# Hall_Effect_Sensors_Panel.net
KiCad netlist of a schematic drawn in Altium Designer
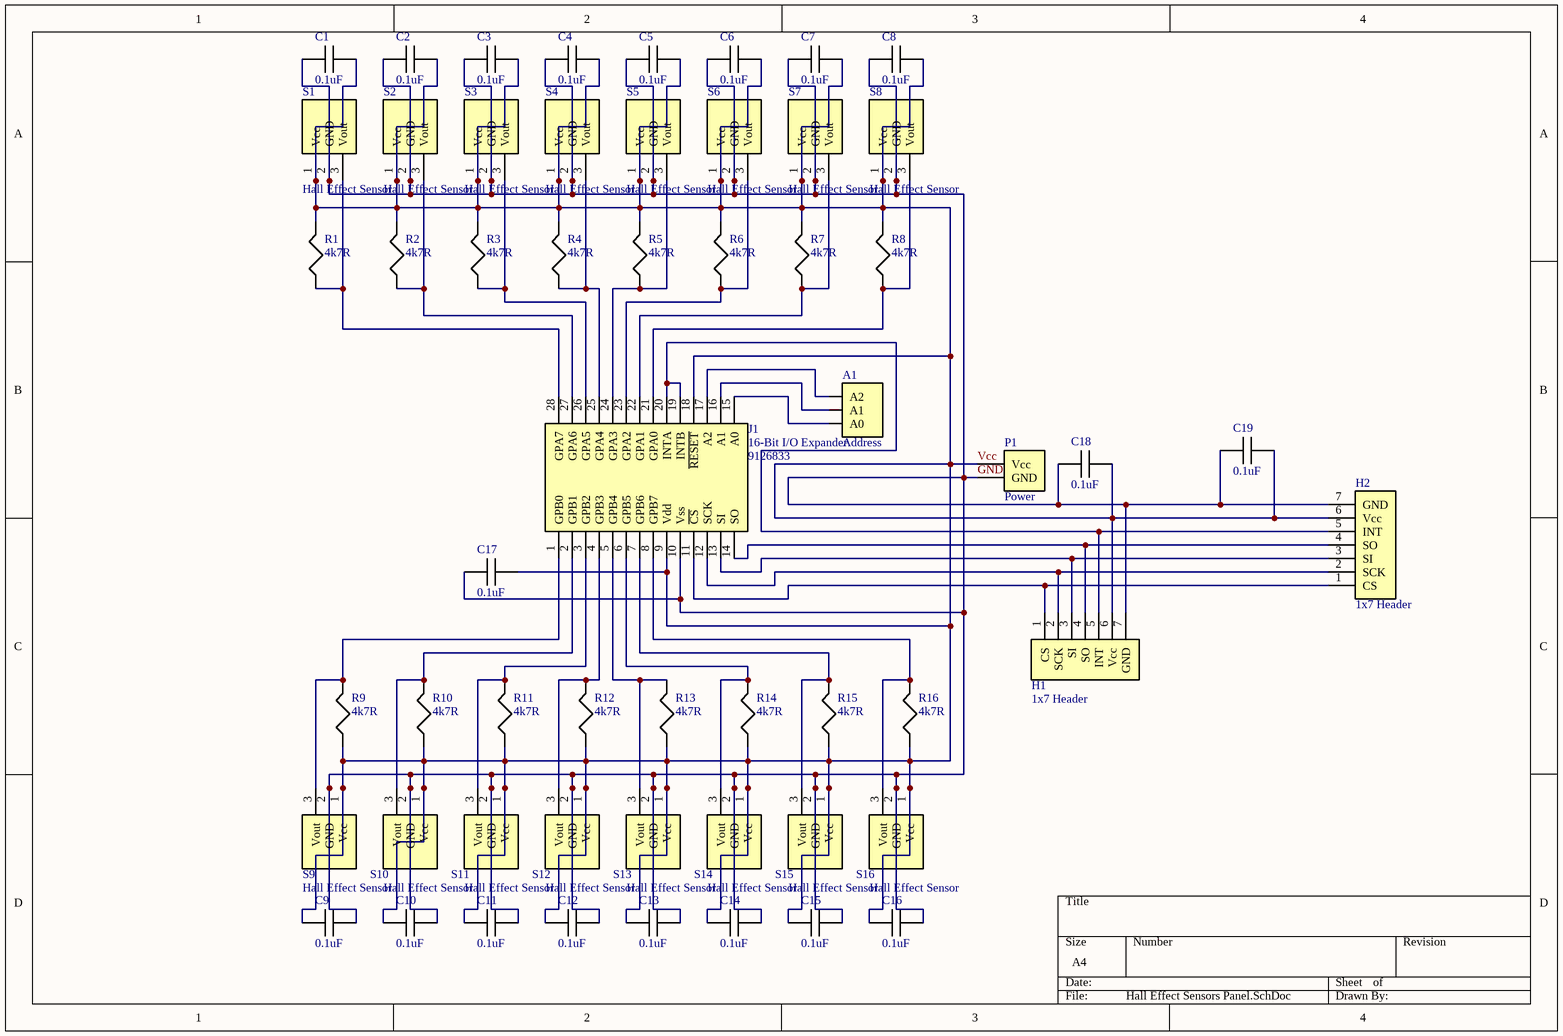
[diagram p0: Hall Effect Sensors Panel.SchDoc]

(export (version "E")
  (design (tool "Eeschema 10.0.6"))
  (components
    (comp (ref "A1")
      (value "Address")
      (footprint "Address")
      (libsource (lib "Hall Effect Sensor Panel Lib") (part "Address"))
    )
    (comp (ref "C1")
      (value "0.1uF")
      (footprint "C320C104K5R5TA")
      (fields
        (field (name "MANUFACTURER") "KEMET")
        (field (name "MANUFACTURER PART NUMBER") "C320C104K5R5TA")
        (field (name "TOLERANCE") "10%")
      )
      (libsource (lib "Hall Effect Sensor Panel Lib") (part "C320C104K5R5TA"))
    )
    (comp (ref "C2")
      (value "0.1uF")
      (footprint "C320C104K5R5TA")
      (fields
        (field (name "MANUFACTURER") "KEMET")
        (field (name "MANUFACTURER PART NUMBER") "C320C104K5R5TA")
        (field (name "TOLERANCE") "10%")
      )
      (libsource (lib "Hall Effect Sensor Panel Lib") (part "C320C104K5R5TA"))
    )
    (comp (ref "C3")
      (value "0.1uF")
      (footprint "C320C104K5R5TA")
      (fields
        (field (name "MANUFACTURER") "KEMET")
        (field (name "MANUFACTURER PART NUMBER") "C320C104K5R5TA")
        (field (name "TOLERANCE") "10%")
      )
      (libsource (lib "Hall Effect Sensor Panel Lib") (part "C320C104K5R5TA"))
    )
    (comp (ref "C4")
      (value "0.1uF")
      (footprint "C320C104K5R5TA")
      (fields
        (field (name "MANUFACTURER") "KEMET")
        (field (name "MANUFACTURER PART NUMBER") "C320C104K5R5TA")
        (field (name "TOLERANCE") "10%")
      )
      (libsource (lib "Hall Effect Sensor Panel Lib") (part "C320C104K5R5TA"))
    )
    (comp (ref "C5")
      (value "0.1uF")
      (footprint "C320C104K5R5TA")
      (fields
        (field (name "MANUFACTURER") "KEMET")
        (field (name "MANUFACTURER PART NUMBER") "C320C104K5R5TA")
        (field (name "TOLERANCE") "10%")
      )
      (libsource (lib "Hall Effect Sensor Panel Lib") (part "C320C104K5R5TA"))
    )
    (comp (ref "C6")
      (value "0.1uF")
      (footprint "C320C104K5R5TA")
      (fields
        (field (name "MANUFACTURER") "KEMET")
        (field (name "MANUFACTURER PART NUMBER") "C320C104K5R5TA")
        (field (name "TOLERANCE") "10%")
      )
      (libsource (lib "Hall Effect Sensor Panel Lib") (part "C320C104K5R5TA"))
    )
    (comp (ref "C7")
      (value "0.1uF")
      (footprint "C320C104K5R5TA")
      (fields
        (field (name "MANUFACTURER") "KEMET")
        (field (name "MANUFACTURER PART NUMBER") "C320C104K5R5TA")
        (field (name "TOLERANCE") "10%")
      )
      (libsource (lib "Hall Effect Sensor Panel Lib") (part "C320C104K5R5TA"))
    )
    (comp (ref "C8")
      (value "0.1uF")
      (footprint "C320C104K5R5TA")
      (fields
        (field (name "MANUFACTURER") "KEMET")
        (field (name "MANUFACTURER PART NUMBER") "C320C104K5R5TA")
        (field (name "TOLERANCE") "10%")
      )
      (libsource (lib "Hall Effect Sensor Panel Lib") (part "C320C104K5R5TA"))
    )
    (comp (ref "C9")
      (value "0.1uF")
      (footprint "C320C104K5R5TA")
      (fields
        (field (name "MANUFACTURER") "KEMET")
        (field (name "MANUFACTURER PART NUMBER") "C320C104K5R5TA")
        (field (name "TOLERANCE") "10%")
      )
      (libsource (lib "Hall Effect Sensor Panel Lib") (part "C320C104K5R5TA"))
    )
    (comp (ref "C10")
      (value "0.1uF")
      (footprint "C320C104K5R5TA")
      (fields
        (field (name "MANUFACTURER") "KEMET")
        (field (name "MANUFACTURER PART NUMBER") "C320C104K5R5TA")
        (field (name "TOLERANCE") "10%")
      )
      (libsource (lib "Hall Effect Sensor Panel Lib") (part "C320C104K5R5TA"))
    )
    (comp (ref "C11")
      (value "0.1uF")
      (footprint "C320C104K5R5TA")
      (fields
        (field (name "MANUFACTURER") "KEMET")
        (field (name "MANUFACTURER PART NUMBER") "C320C104K5R5TA")
        (field (name "TOLERANCE") "10%")
      )
      (libsource (lib "Hall Effect Sensor Panel Lib") (part "C320C104K5R5TA"))
    )
    (comp (ref "C12")
      (value "0.1uF")
      (footprint "C320C104K5R5TA")
      (fields
        (field (name "MANUFACTURER") "KEMET")
        (field (name "MANUFACTURER PART NUMBER") "C320C104K5R5TA")
        (field (name "TOLERANCE") "10%")
      )
      (libsource (lib "Hall Effect Sensor Panel Lib") (part "C320C104K5R5TA"))
    )
    (comp (ref "C13")
      (value "0.1uF")
      (footprint "C320C104K5R5TA")
      (fields
        (field (name "MANUFACTURER") "KEMET")
        (field (name "MANUFACTURER PART NUMBER") "C320C104K5R5TA")
        (field (name "TOLERANCE") "10%")
      )
      (libsource (lib "Hall Effect Sensor Panel Lib") (part "C320C104K5R5TA"))
    )
    (comp (ref "C14")
      (value "0.1uF")
      (footprint "C320C104K5R5TA")
      (fields
        (field (name "MANUFACTURER") "KEMET")
        (field (name "MANUFACTURER PART NUMBER") "C320C104K5R5TA")
        (field (name "TOLERANCE") "10%")
      )
      (libsource (lib "Hall Effect Sensor Panel Lib") (part "C320C104K5R5TA"))
    )
    (comp (ref "C15")
      (value "0.1uF")
      (footprint "C320C104K5R5TA")
      (fields
        (field (name "MANUFACTURER") "KEMET")
        (field (name "MANUFACTURER PART NUMBER") "C320C104K5R5TA")
        (field (name "TOLERANCE") "10%")
      )
      (libsource (lib "Hall Effect Sensor Panel Lib") (part "C320C104K5R5TA"))
    )
    (comp (ref "C16")
      (value "0.1uF")
      (footprint "C320C104K5R5TA")
      (fields
        (field (name "MANUFACTURER") "KEMET")
        (field (name "MANUFACTURER PART NUMBER") "C320C104K5R5TA")
        (field (name "TOLERANCE") "10%")
      )
      (libsource (lib "Hall Effect Sensor Panel Lib") (part "C320C104K5R5TA"))
    )
    (comp (ref "C17")
      (value "0.1uF")
      (footprint "C320C104K5R5TA")
      (fields
        (field (name "MANUFACTURER") "KEMET")
        (field (name "MANUFACTURER PART NUMBER") "C320C104K5R5TA")
        (field (name "TOLERANCE") "10%")
      )
      (libsource (lib "Hall Effect Sensor Panel Lib") (part "C320C104K5R5TA"))
    )
    (comp (ref "C18")
      (value "0.1uF")
      (footprint "C320C104K5R5TA")
      (fields
        (field (name "MANUFACTURER") "KEMET")
        (field (name "MANUFACTURER PART NUMBER") "C320C104K5R5TA")
        (field (name "TOLERANCE") "10%")
      )
      (libsource (lib "Hall Effect Sensor Panel Lib") (part "C320C104K5R5TA"))
    )
    (comp (ref "C19")
      (value "0.1uF")
      (footprint "C320C104K5R5TA")
      (fields
        (field (name "MANUFACTURER") "KEMET")
        (field (name "MANUFACTURER PART NUMBER") "C320C104K5R5TA")
        (field (name "TOLERANCE") "10%")
      )
      (libsource (lib "Hall Effect Sensor Panel Lib") (part "C320C104K5R5TA"))
    )
    (comp (ref "H1")
      (value "1x7 Header")
      (footprint "Molex")
      (description "CONN HEADER VERT 7POS 2.54MM")
      (fields (field (name "MANUFACTURER") "Molex") (field (name "MANUFACTURER PART NUMBER") "22-23-2071"))
      (libsource (lib "") (part "22-23-2071_1"))
    )
    (comp (ref "H2")
      (value "1x7 Header")
      (footprint "Molex")
      (description "CONN HEADER VERT 7POS 2.54MM")
      (fields (field (name "MANUFACTURER") "Molex") (field (name "MANUFACTURER PART NUMBER") "22-23-2071"))
      (libsource (lib "Hall Effect Sensor Panel Lib") (part "22-23-2071"))
    )
    (comp (ref "J1")
      (value "16-Bit I/O Expander")
      (footprint "MCP23S17-E/SP")
      (fields
        (field (name "MANUFACTURER") "Microchip")
        (field (name "MANUFACTURER PART NUMBER") "MCP23S17-E/SP")
        (field (name "SUPPLIER PART NUMBER 1") "9126833")
        (field (name "TOLERANCE") "5%")
      )
      (libsource (lib "Hall Effect Sensor Panel Lib") (part "MCP23S17-E/SP"))
    )
    (comp (ref "P1")
      (value "Power")
      (footprint "Power")
      (libsource (lib "Hall Effect Sensor Panel Lib") (part "Power"))
    )
    (comp (ref "R1")
      (value "4k7R")
      (footprint "CFR100J4K7")
      (fields
        (field (name "MANUFACTURER") "TE Connectivity")
        (field (name "MANUFACTURER PART NUMBER") "CFR100J4K7")
        (field (name "TOLERANCE") "5%")
      )
      (libsource (lib "Hall Effect Sensor Panel Lib") (part "CFR100J4K7"))
    )
    (comp (ref "R2")
      (value "4k7R")
      (footprint "CFR100J4K7")
      (fields
        (field (name "MANUFACTURER") "TE Connectivity")
        (field (name "MANUFACTURER PART NUMBER") "CFR100J4K7")
        (field (name "TOLERANCE") "5%")
      )
      (libsource (lib "Hall Effect Sensor Panel Lib") (part "CFR100J4K7"))
    )
    (comp (ref "R3")
      (value "4k7R")
      (footprint "CFR100J4K7")
      (fields
        (field (name "MANUFACTURER") "TE Connectivity")
        (field (name "MANUFACTURER PART NUMBER") "CFR100J4K7")
        (field (name "TOLERANCE") "5%")
      )
      (libsource (lib "Hall Effect Sensor Panel Lib") (part "CFR100J4K7"))
    )
    (comp (ref "R4")
      (value "4k7R")
      (footprint "CFR100J4K7")
      (fields
        (field (name "MANUFACTURER") "TE Connectivity")
        (field (name "MANUFACTURER PART NUMBER") "CFR100J4K7")
        (field (name "TOLERANCE") "5%")
      )
      (libsource (lib "Hall Effect Sensor Panel Lib") (part "CFR100J4K7"))
    )
    (comp (ref "R5")
      (value "4k7R")
      (footprint "CFR100J4K7")
      (fields
        (field (name "MANUFACTURER") "TE Connectivity")
        (field (name "MANUFACTURER PART NUMBER") "CFR100J4K7")
        (field (name "TOLERANCE") "5%")
      )
      (libsource (lib "Hall Effect Sensor Panel Lib") (part "CFR100J4K7"))
    )
    (comp (ref "R6")
      (value "4k7R")
      (footprint "CFR100J4K7")
      (fields
        (field (name "MANUFACTURER") "TE Connectivity")
        (field (name "MANUFACTURER PART NUMBER") "CFR100J4K7")
        (field (name "TOLERANCE") "5%")
      )
      (libsource (lib "Hall Effect Sensor Panel Lib") (part "CFR100J4K7"))
    )
    (comp (ref "R7")
      (value "4k7R")
      (footprint "CFR100J4K7")
      (fields
        (field (name "MANUFACTURER") "TE Connectivity")
        (field (name "MANUFACTURER PART NUMBER") "CFR100J4K7")
        (field (name "TOLERANCE") "5%")
      )
      (libsource (lib "Hall Effect Sensor Panel Lib") (part "CFR100J4K7"))
    )
    (comp (ref "R8")
      (value "4k7R")
      (footprint "CFR100J4K7")
      (fields
        (field (name "MANUFACTURER") "TE Connectivity")
        (field (name "MANUFACTURER PART NUMBER") "CFR100J4K7")
        (field (name "TOLERANCE") "5%")
      )
      (libsource (lib "Hall Effect Sensor Panel Lib") (part "CFR100J4K7"))
    )
    (comp (ref "R9")
      (value "4k7R")
      (footprint "CFR100J4K7")
      (fields
        (field (name "MANUFACTURER") "TE Connectivity")
        (field (name "MANUFACTURER PART NUMBER") "CFR100J4K7")
        (field (name "TOLERANCE") "5%")
      )
      (libsource (lib "Hall Effect Sensor Panel Lib") (part "CFR100J4K7"))
    )
    (comp (ref "R10")
      (value "4k7R")
      (footprint "CFR100J4K7")
      (fields
        (field (name "MANUFACTURER") "TE Connectivity")
        (field (name "MANUFACTURER PART NUMBER") "CFR100J4K7")
        (field (name "TOLERANCE") "5%")
      )
      (libsource (lib "Hall Effect Sensor Panel Lib") (part "CFR100J4K7"))
    )
    (comp (ref "R11")
      (value "4k7R")
      (footprint "CFR100J4K7")
      (fields
        (field (name "MANUFACTURER") "TE Connectivity")
        (field (name "MANUFACTURER PART NUMBER") "CFR100J4K7")
        (field (name "TOLERANCE") "5%")
      )
      (libsource (lib "Hall Effect Sensor Panel Lib") (part "CFR100J4K7"))
    )
    (comp (ref "R12")
      (value "4k7R")
      (footprint "CFR100J4K7")
      (fields
        (field (name "MANUFACTURER") "TE Connectivity")
        (field (name "MANUFACTURER PART NUMBER") "CFR100J4K7")
        (field (name "TOLERANCE") "5%")
      )
      (libsource (lib "Hall Effect Sensor Panel Lib") (part "CFR100J4K7"))
    )
    (comp (ref "R13")
      (value "4k7R")
      (footprint "CFR100J4K7")
      (fields
        (field (name "MANUFACTURER") "TE Connectivity")
        (field (name "MANUFACTURER PART NUMBER") "CFR100J4K7")
        (field (name "TOLERANCE") "5%")
      )
      (libsource (lib "Hall Effect Sensor Panel Lib") (part "CFR100J4K7"))
    )
    (comp (ref "R14")
      (value "4k7R")
      (footprint "CFR100J4K7")
      (fields
        (field (name "MANUFACTURER") "TE Connectivity")
        (field (name "MANUFACTURER PART NUMBER") "CFR100J4K7")
        (field (name "TOLERANCE") "5%")
      )
      (libsource (lib "Hall Effect Sensor Panel Lib") (part "CFR100J4K7"))
    )
    (comp (ref "R15")
      (value "4k7R")
      (footprint "CFR100J4K7")
      (fields
        (field (name "MANUFACTURER") "TE Connectivity")
        (field (name "MANUFACTURER PART NUMBER") "CFR100J4K7")
        (field (name "TOLERANCE") "5%")
      )
      (libsource (lib "Hall Effect Sensor Panel Lib") (part "CFR100J4K7"))
    )
    (comp (ref "R16")
      (value "4k7R")
      (footprint "CFR100J4K7")
      (fields
        (field (name "MANUFACTURER") "TE Connectivity")
        (field (name "MANUFACTURER PART NUMBER") "CFR100J4K7")
        (field (name "TOLERANCE") "5%")
      )
      (libsource (lib "Hall Effect Sensor Panel Lib") (part "CFR100J4K7"))
    )
    (comp (ref "S1")
      (value "Hall Effect Sensor")
      (footprint "A1104EUA-T")
      (description "ALLEGRO MICROSYSTEMS - A1104EUA-T - IC, HALL-EFFECT SWITCH SIP-3")
      (fields
        (field (name "MANUFACTURER") "Allegro MicroSystems")
        (field (name "MANUFACTURER PART NUMBER") "A1104EUA-T")
      )
      (libsource (lib "Hall Effect Sensor Panel Lib") (part "A1104EUA-T"))
    )
    (comp (ref "S2")
      (value "Hall Effect Sensor")
      (footprint "A1104EUA-T")
      (description "ALLEGRO MICROSYSTEMS - A1104EUA-T - IC, HALL-EFFECT SWITCH SIP-3")
      (fields
        (field (name "MANUFACTURER") "Allegro MicroSystems")
        (field (name "MANUFACTURER PART NUMBER") "A1104EUA-T")
      )
      (libsource (lib "Hall Effect Sensor Panel Lib") (part "A1104EUA-T"))
    )
    (comp (ref "S3")
      (value "Hall Effect Sensor")
      (footprint "A1104EUA-T")
      (description "ALLEGRO MICROSYSTEMS - A1104EUA-T - IC, HALL-EFFECT SWITCH SIP-3")
      (fields
        (field (name "MANUFACTURER") "Allegro MicroSystems")
        (field (name "MANUFACTURER PART NUMBER") "A1104EUA-T")
      )
      (libsource (lib "Hall Effect Sensor Panel Lib") (part "A1104EUA-T"))
    )
    (comp (ref "S4")
      (value "Hall Effect Sensor")
      (footprint "A1104EUA-T")
      (description "ALLEGRO MICROSYSTEMS - A1104EUA-T - IC, HALL-EFFECT SWITCH SIP-3")
      (fields
        (field (name "MANUFACTURER") "Allegro MicroSystems")
        (field (name "MANUFACTURER PART NUMBER") "A1104EUA-T")
      )
      (libsource (lib "Hall Effect Sensor Panel Lib") (part "A1104EUA-T"))
    )
    (comp (ref "S5")
      (value "Hall Effect Sensor")
      (footprint "A1104EUA-T")
      (description "ALLEGRO MICROSYSTEMS - A1104EUA-T - IC, HALL-EFFECT SWITCH SIP-3")
      (fields
        (field (name "MANUFACTURER") "Allegro MicroSystems")
        (field (name "MANUFACTURER PART NUMBER") "A1104EUA-T")
      )
      (libsource (lib "Hall Effect Sensor Panel Lib") (part "A1104EUA-T"))
    )
    (comp (ref "S6")
      (value "Hall Effect Sensor")
      (footprint "A1104EUA-T")
      (description "ALLEGRO MICROSYSTEMS - A1104EUA-T - IC, HALL-EFFECT SWITCH SIP-3")
      (fields
        (field (name "MANUFACTURER") "Allegro MicroSystems")
        (field (name "MANUFACTURER PART NUMBER") "A1104EUA-T")
      )
      (libsource (lib "Hall Effect Sensor Panel Lib") (part "A1104EUA-T"))
    )
    (comp (ref "S7")
      (value "Hall Effect Sensor")
      (footprint "A1104EUA-T")
      (description "ALLEGRO MICROSYSTEMS - A1104EUA-T - IC, HALL-EFFECT SWITCH SIP-3")
      (fields
        (field (name "MANUFACTURER") "Allegro MicroSystems")
        (field (name "MANUFACTURER PART NUMBER") "A1104EUA-T")
      )
      (libsource (lib "Hall Effect Sensor Panel Lib") (part "A1104EUA-T"))
    )
    (comp (ref "S8")
      (value "Hall Effect Sensor")
      (footprint "A1104EUA-T")
      (description "ALLEGRO MICROSYSTEMS - A1104EUA-T - IC, HALL-EFFECT SWITCH SIP-3")
      (fields
        (field (name "MANUFACTURER") "Allegro MicroSystems")
        (field (name "MANUFACTURER PART NUMBER") "A1104EUA-T")
      )
      (libsource (lib "Hall Effect Sensor Panel Lib") (part "A1104EUA-T"))
    )
    (comp (ref "S9")
      (value "Hall Effect Sensor")
      (footprint "A1104EUA-T")
      (description "ALLEGRO MICROSYSTEMS - A1104EUA-T - IC, HALL-EFFECT SWITCH SIP-3")
      (fields
        (field (name "MANUFACTURER") "Allegro MicroSystems")
        (field (name "MANUFACTURER PART NUMBER") "A1104EUA-T")
      )
      (libsource (lib "") (part "A1104EUA-T_1"))
    )
    (comp (ref "S10")
      (value "Hall Effect Sensor")
      (footprint "A1104EUA-T")
      (description "ALLEGRO MICROSYSTEMS - A1104EUA-T - IC, HALL-EFFECT SWITCH SIP-3")
      (fields
        (field (name "MANUFACTURER") "Allegro MicroSystems")
        (field (name "MANUFACTURER PART NUMBER") "A1104EUA-T")
      )
      (libsource (lib "") (part "A1104EUA-T_1"))
    )
    (comp (ref "S11")
      (value "Hall Effect Sensor")
      (footprint "A1104EUA-T")
      (description "ALLEGRO MICROSYSTEMS - A1104EUA-T - IC, HALL-EFFECT SWITCH SIP-3")
      (fields
        (field (name "MANUFACTURER") "Allegro MicroSystems")
        (field (name "MANUFACTURER PART NUMBER") "A1104EUA-T")
      )
      (libsource (lib "") (part "A1104EUA-T_1"))
    )
    (comp (ref "S12")
      (value "Hall Effect Sensor")
      (footprint "A1104EUA-T")
      (description "ALLEGRO MICROSYSTEMS - A1104EUA-T - IC, HALL-EFFECT SWITCH SIP-3")
      (fields
        (field (name "MANUFACTURER") "Allegro MicroSystems")
        (field (name "MANUFACTURER PART NUMBER") "A1104EUA-T")
      )
      (libsource (lib "") (part "A1104EUA-T_1"))
    )
    (comp (ref "S13")
      (value "Hall Effect Sensor")
      (footprint "A1104EUA-T")
      (description "ALLEGRO MICROSYSTEMS - A1104EUA-T - IC, HALL-EFFECT SWITCH SIP-3")
      (fields
        (field (name "MANUFACTURER") "Allegro MicroSystems")
        (field (name "MANUFACTURER PART NUMBER") "A1104EUA-T")
      )
      (libsource (lib "") (part "A1104EUA-T_1"))
    )
    (comp (ref "S14")
      (value "Hall Effect Sensor")
      (footprint "A1104EUA-T")
      (description "ALLEGRO MICROSYSTEMS - A1104EUA-T - IC, HALL-EFFECT SWITCH SIP-3")
      (fields
        (field (name "MANUFACTURER") "Allegro MicroSystems")
        (field (name "MANUFACTURER PART NUMBER") "A1104EUA-T")
      )
      (libsource (lib "") (part "A1104EUA-T_1"))
    )
    (comp (ref "S15")
      (value "Hall Effect Sensor")
      (footprint "A1104EUA-T")
      (description "ALLEGRO MICROSYSTEMS - A1104EUA-T - IC, HALL-EFFECT SWITCH SIP-3")
      (fields
        (field (name "MANUFACTURER") "Allegro MicroSystems")
        (field (name "MANUFACTURER PART NUMBER") "A1104EUA-T")
      )
      (libsource (lib "") (part "A1104EUA-T_1"))
    )
    (comp (ref "S16")
      (value "Hall Effect Sensor")
      (footprint "A1104EUA-T")
      (description "ALLEGRO MICROSYSTEMS - A1104EUA-T - IC, HALL-EFFECT SWITCH SIP-3")
      (fields
        (field (name "MANUFACTURER") "Allegro MicroSystems")
        (field (name "MANUFACTURER PART NUMBER") "A1104EUA-T")
      )
      (libsource (lib "") (part "A1104EUA-T_1"))
    )
  )
  (nets
    (net (code "1") (name "/GND") (class "Default")
      (node (ref "C1") (pin "1") (pinfunction "48_1") (pintype "passive"))
      (node (ref "C10") (pin "2") (pinfunction "2_2") (pintype "passive"))
      (node (ref "C11") (pin "2") (pinfunction "2_2") (pintype "passive"))
      (node (ref "C12") (pin "2") (pinfunction "2_2") (pintype "passive"))
      (node (ref "C13") (pin "2") (pinfunction "2_2") (pintype "passive"))
      (node (ref "C14") (pin "2") (pinfunction "2_2") (pintype "passive"))
      (node (ref "C15") (pin "2") (pinfunction "2_2") (pintype "passive"))
      (node (ref "C16") (pin "2") (pinfunction "2_2") (pintype "passive"))
      (node (ref "C17") (pin "1") (pinfunction "48_1") (pintype "passive"))
      (node (ref "C18") (pin "1") (pinfunction "48_1") (pintype "passive"))
      (node (ref "C19") (pin "1") (pinfunction "48_1") (pintype "passive"))
      (node (ref "C2") (pin "1") (pinfunction "48_1") (pintype "passive"))
      (node (ref "C3") (pin "1") (pinfunction "48_1") (pintype "passive"))
      (node (ref "C4") (pin "1") (pinfunction "48_1") (pintype "passive"))
      (node (ref "C5") (pin "1") (pinfunction "48_1") (pintype "passive"))
      (node (ref "C6") (pin "1") (pinfunction "48_1") (pintype "passive"))
      (node (ref "C7") (pin "1") (pinfunction "48_1") (pintype "passive"))
      (node (ref "C8") (pin "1") (pinfunction "48_1") (pintype "passive"))
      (node (ref "C9") (pin "2") (pinfunction "2_2") (pintype "passive"))
      (node (ref "H1") (pin "7") (pinfunction "GND_7") (pintype "passive"))
      (node (ref "H2") (pin "7") (pinfunction "GND_7") (pintype "passive"))
      (node (ref "J1") (pin "10") (pinfunction "Vss_10") (pintype "passive"))
      (node (ref "P1") (pin "2") (pinfunction "GND_2") (pintype "passive"))
      (node (ref "S1") (pin "2") (pinfunction "GND_2") (pintype "passive"))
      (node (ref "S10") (pin "2") (pinfunction "GND_2") (pintype "passive"))
      (node (ref "S11") (pin "2") (pinfunction "GND_2") (pintype "passive"))
      (node (ref "S12") (pin "2") (pinfunction "GND_2") (pintype "passive"))
      (node (ref "S13") (pin "2") (pinfunction "GND_2") (pintype "passive"))
      (node (ref "S14") (pin "2") (pinfunction "GND_2") (pintype "passive"))
      (node (ref "S15") (pin "2") (pinfunction "GND_2") (pintype "passive"))
      (node (ref "S16") (pin "2") (pinfunction "GND_2") (pintype "passive"))
      (node (ref "S2") (pin "2") (pinfunction "GND_2") (pintype "passive"))
      (node (ref "S3") (pin "2") (pinfunction "GND_2") (pintype "passive"))
      (node (ref "S4") (pin "2") (pinfunction "GND_2") (pintype "passive"))
      (node (ref "S5") (pin "2") (pinfunction "GND_2") (pintype "passive"))
      (node (ref "S6") (pin "2") (pinfunction "GND_2") (pintype "passive"))
      (node (ref "S7") (pin "2") (pinfunction "GND_2") (pintype "passive"))
      (node (ref "S8") (pin "2") (pinfunction "GND_2") (pintype "passive"))
      (node (ref "S9") (pin "2") (pinfunction "GND_2") (pintype "passive"))
    )
    (net (code "2") (name "/Vcc") (class "Default")
      (node (ref "C1") (pin "2") (pinfunction "2_2") (pintype "passive"))
      (node (ref "C10") (pin "1") (pinfunction "48_1") (pintype "passive"))
      (node (ref "C11") (pin "1") (pinfunction "48_1") (pintype "passive"))
      (node (ref "C12") (pin "1") (pinfunction "48_1") (pintype "passive"))
      (node (ref "C13") (pin "1") (pinfunction "48_1") (pintype "passive"))
      (node (ref "C14") (pin "1") (pinfunction "48_1") (pintype "passive"))
      (node (ref "C15") (pin "1") (pinfunction "48_1") (pintype "passive"))
      (node (ref "C16") (pin "1") (pinfunction "48_1") (pintype "passive"))
      (node (ref "C17") (pin "2") (pinfunction "2_2") (pintype "passive"))
      (node (ref "C18") (pin "2") (pinfunction "2_2") (pintype "passive"))
      (node (ref "C19") (pin "2") (pinfunction "2_2") (pintype "passive"))
      (node (ref "C2") (pin "2") (pinfunction "2_2") (pintype "passive"))
      (node (ref "C3") (pin "2") (pinfunction "2_2") (pintype "passive"))
      (node (ref "C4") (pin "2") (pinfunction "2_2") (pintype "passive"))
      (node (ref "C5") (pin "2") (pinfunction "2_2") (pintype "passive"))
      (node (ref "C6") (pin "2") (pinfunction "2_2") (pintype "passive"))
      (node (ref "C7") (pin "2") (pinfunction "2_2") (pintype "passive"))
      (node (ref "C8") (pin "2") (pinfunction "2_2") (pintype "passive"))
      (node (ref "C9") (pin "1") (pinfunction "48_1") (pintype "passive"))
      (node (ref "H1") (pin "6") (pinfunction "Vcc_6") (pintype "passive"))
      (node (ref "H2") (pin "6") (pinfunction "Vcc_6") (pintype "passive"))
      (node (ref "J1") (pin "18") (pinfunction "~{RESET}_18") (pintype "passive"))
      (node (ref "J1") (pin "9") (pinfunction "Vdd_9") (pintype "passive"))
      (node (ref "P1") (pin "1") (pinfunction "Vcc_1") (pintype "passive"))
      (node (ref "R1") (pin "2") (pinfunction "2_2") (pintype "passive"))
      (node (ref "R10") (pin "1") (pinfunction "1_1") (pintype "passive"))
      (node (ref "R11") (pin "1") (pinfunction "1_1") (pintype "passive"))
      (node (ref "R12") (pin "1") (pinfunction "1_1") (pintype "passive"))
      (node (ref "R13") (pin "1") (pinfunction "1_1") (pintype "passive"))
      (node (ref "R14") (pin "1") (pinfunction "1_1") (pintype "passive"))
      (node (ref "R15") (pin "1") (pinfunction "1_1") (pintype "passive"))
      (node (ref "R16") (pin "1") (pinfunction "1_1") (pintype "passive"))
      (node (ref "R2") (pin "2") (pinfunction "2_2") (pintype "passive"))
      (node (ref "R3") (pin "2") (pinfunction "2_2") (pintype "passive"))
      (node (ref "R4") (pin "2") (pinfunction "2_2") (pintype "passive"))
      (node (ref "R5") (pin "2") (pinfunction "2_2") (pintype "passive"))
      (node (ref "R6") (pin "2") (pinfunction "2_2") (pintype "passive"))
      (node (ref "R7") (pin "2") (pinfunction "2_2") (pintype "passive"))
      (node (ref "R8") (pin "2") (pinfunction "2_2") (pintype "passive"))
      (node (ref "R9") (pin "1") (pinfunction "1_1") (pintype "passive"))
      (node (ref "S1") (pin "1") (pinfunction "Vcc_1") (pintype "passive"))
      (node (ref "S10") (pin "1") (pinfunction "Vcc_1") (pintype "passive"))
      (node (ref "S11") (pin "1") (pinfunction "Vcc_1") (pintype "passive"))
      (node (ref "S12") (pin "1") (pinfunction "Vcc_1") (pintype "passive"))
      (node (ref "S13") (pin "1") (pinfunction "Vcc_1") (pintype "passive"))
      (node (ref "S14") (pin "1") (pinfunction "Vcc_1") (pintype "passive"))
      (node (ref "S15") (pin "1") (pinfunction "Vcc_1") (pintype "passive"))
      (node (ref "S16") (pin "1") (pinfunction "Vcc_1") (pintype "passive"))
      (node (ref "S2") (pin "1") (pinfunction "Vcc_1") (pintype "passive"))
      (node (ref "S3") (pin "1") (pinfunction "Vcc_1") (pintype "passive"))
      (node (ref "S4") (pin "1") (pinfunction "Vcc_1") (pintype "passive"))
      (node (ref "S5") (pin "1") (pinfunction "Vcc_1") (pintype "passive"))
      (node (ref "S6") (pin "1") (pinfunction "Vcc_1") (pintype "passive"))
      (node (ref "S7") (pin "1") (pinfunction "Vcc_1") (pintype "passive"))
      (node (ref "S8") (pin "1") (pinfunction "Vcc_1") (pintype "passive"))
      (node (ref "S9") (pin "1") (pinfunction "Vcc_1") (pintype "passive"))
    )
    (net (code "3") (name "Net-(A1-A0)") (class "Default")
      (node (ref "A1") (pin "1") (pinfunction "A0_1") (pintype "passive"))
      (node (ref "J1") (pin "15") (pinfunction "A0_15") (pintype "passive"))
    )
    (net (code "4") (name "Net-(A1-A1)") (class "Default")
      (node (ref "A1") (pin "2") (pinfunction "A1_2") (pintype "passive"))
      (node (ref "J1") (pin "16") (pinfunction "A1_16") (pintype "passive"))
    )
    (net (code "5") (name "Net-(A1-A2)") (class "Default")
      (node (ref "A1") (pin "3") (pinfunction "A2_3") (pintype "passive"))
      (node (ref "J1") (pin "17") (pinfunction "A2_17") (pintype "passive"))
    )
    (net (code "6") (name "Net-(H1-CS)") (class "Default")
      (node (ref "H1") (pin "1") (pinfunction "CS_1") (pintype "passive"))
      (node (ref "H2") (pin "1") (pinfunction "CS_1") (pintype "passive"))
      (node (ref "J1") (pin "11") (pinfunction "~{CS}_11") (pintype "passive"))
    )
    (net (code "7") (name "Net-(H1-INT)") (class "Default")
      (node (ref "H1") (pin "5") (pinfunction "INT_5") (pintype "passive"))
      (node (ref "H2") (pin "5") (pinfunction "INT_5") (pintype "passive"))
      (node (ref "J1") (pin "19") (pinfunction "INTB_19") (pintype "passive"))
      (node (ref "J1") (pin "20") (pinfunction "INTA_20") (pintype "passive"))
    )
    (net (code "8") (name "Net-(H1-SCK)") (class "Default")
      (node (ref "H1") (pin "2") (pinfunction "SCK_2") (pintype "passive"))
      (node (ref "H2") (pin "2") (pinfunction "SCK_2") (pintype "passive"))
      (node (ref "J1") (pin "12") (pinfunction "SCK_12") (pintype "passive"))
    )
    (net (code "9") (name "Net-(H1-SI)") (class "Default")
      (node (ref "H1") (pin "3") (pinfunction "SI_3") (pintype "passive"))
      (node (ref "H2") (pin "3") (pinfunction "SI_3") (pintype "passive"))
      (node (ref "J1") (pin "13") (pinfunction "SI_13") (pintype "passive"))
    )
    (net (code "10") (name "Net-(H1-SO)") (class "Default")
      (node (ref "H1") (pin "4") (pinfunction "SO_4") (pintype "passive"))
      (node (ref "H2") (pin "4") (pinfunction "SO_4") (pintype "passive"))
      (node (ref "J1") (pin "14") (pinfunction "SO_14") (pintype "passive"))
    )
    (net (code "11") (name "Net-(J1-GPA0)") (class "Default")
      (node (ref "J1") (pin "21") (pinfunction "GPA0_21") (pintype "passive"))
      (node (ref "R8") (pin "1") (pinfunction "1_1") (pintype "passive"))
      (node (ref "S8") (pin "3") (pinfunction "Vout_3") (pintype "passive"))
    )
    (net (code "12") (name "Net-(J1-GPA1)") (class "Default")
      (node (ref "J1") (pin "22") (pinfunction "GPA1_22") (pintype "passive"))
      (node (ref "R7") (pin "1") (pinfunction "1_1") (pintype "passive"))
      (node (ref "S7") (pin "3") (pinfunction "Vout_3") (pintype "passive"))
    )
    (net (code "13") (name "Net-(J1-GPA2)") (class "Default")
      (node (ref "J1") (pin "23") (pinfunction "GPA2_23") (pintype "passive"))
      (node (ref "R6") (pin "1") (pinfunction "1_1") (pintype "passive"))
      (node (ref "S6") (pin "3") (pinfunction "Vout_3") (pintype "passive"))
    )
    (net (code "14") (name "Net-(J1-GPA3)") (class "Default")
      (node (ref "J1") (pin "24") (pinfunction "GPA3_24") (pintype "passive"))
      (node (ref "R5") (pin "1") (pinfunction "1_1") (pintype "passive"))
      (node (ref "S5") (pin "3") (pinfunction "Vout_3") (pintype "passive"))
    )
    (net (code "15") (name "Net-(J1-GPA4)") (class "Default")
      (node (ref "J1") (pin "25") (pinfunction "GPA4_25") (pintype "passive"))
      (node (ref "R4") (pin "1") (pinfunction "1_1") (pintype "passive"))
      (node (ref "S4") (pin "3") (pinfunction "Vout_3") (pintype "passive"))
    )
    (net (code "16") (name "Net-(J1-GPA5)") (class "Default")
      (node (ref "J1") (pin "26") (pinfunction "GPA5_26") (pintype "passive"))
      (node (ref "R3") (pin "1") (pinfunction "1_1") (pintype "passive"))
      (node (ref "S3") (pin "3") (pinfunction "Vout_3") (pintype "passive"))
    )
    (net (code "17") (name "Net-(J1-GPA6)") (class "Default")
      (node (ref "J1") (pin "27") (pinfunction "GPA6_27") (pintype "passive"))
      (node (ref "R2") (pin "1") (pinfunction "1_1") (pintype "passive"))
      (node (ref "S2") (pin "3") (pinfunction "Vout_3") (pintype "passive"))
    )
    (net (code "18") (name "Net-(J1-GPA7)") (class "Default")
      (node (ref "J1") (pin "28") (pinfunction "GPA7_28") (pintype "passive"))
      (node (ref "R1") (pin "1") (pinfunction "1_1") (pintype "passive"))
      (node (ref "S1") (pin "3") (pinfunction "Vout_3") (pintype "passive"))
    )
    (net (code "19") (name "Net-(J1-GPB0)") (class "Default")
      (node (ref "J1") (pin "1") (pinfunction "GPB0_1") (pintype "passive"))
      (node (ref "R9") (pin "2") (pinfunction "2_2") (pintype "passive"))
      (node (ref "S9") (pin "3") (pinfunction "Vout_3") (pintype "passive"))
    )
    (net (code "20") (name "Net-(J1-GPB1)") (class "Default")
      (node (ref "J1") (pin "2") (pinfunction "GPB1_2") (pintype "passive"))
      (node (ref "R10") (pin "2") (pinfunction "2_2") (pintype "passive"))
      (node (ref "S10") (pin "3") (pinfunction "Vout_3") (pintype "passive"))
    )
    (net (code "21") (name "Net-(J1-GPB2)") (class "Default")
      (node (ref "J1") (pin "3") (pinfunction "GPB2_3") (pintype "passive"))
      (node (ref "R11") (pin "2") (pinfunction "2_2") (pintype "passive"))
      (node (ref "S11") (pin "3") (pinfunction "Vout_3") (pintype "passive"))
    )
    (net (code "22") (name "Net-(J1-GPB3)") (class "Default")
      (node (ref "J1") (pin "4") (pinfunction "GPB3_4") (pintype "passive"))
      (node (ref "R12") (pin "2") (pinfunction "2_2") (pintype "passive"))
      (node (ref "S12") (pin "3") (pinfunction "Vout_3") (pintype "passive"))
    )
    (net (code "23") (name "Net-(J1-GPB4)") (class "Default")
      (node (ref "J1") (pin "5") (pinfunction "GPB4_5") (pintype "passive"))
      (node (ref "R13") (pin "2") (pinfunction "2_2") (pintype "passive"))
      (node (ref "S13") (pin "3") (pinfunction "Vout_3") (pintype "passive"))
    )
    (net (code "24") (name "Net-(J1-GPB5)") (class "Default")
      (node (ref "J1") (pin "6") (pinfunction "GPB5_6") (pintype "passive"))
      (node (ref "R14") (pin "2") (pinfunction "2_2") (pintype "passive"))
      (node (ref "S14") (pin "3") (pinfunction "Vout_3") (pintype "passive"))
    )
    (net (code "25") (name "Net-(J1-GPB6)") (class "Default")
      (node (ref "J1") (pin "7") (pinfunction "GPB6_7") (pintype "passive"))
      (node (ref "R15") (pin "2") (pinfunction "2_2") (pintype "passive"))
      (node (ref "S15") (pin "3") (pinfunction "Vout_3") (pintype "passive"))
    )
    (net (code "26") (name "Net-(J1-GPB7)") (class "Default")
      (node (ref "J1") (pin "8") (pinfunction "GPB7_8") (pintype "passive"))
      (node (ref "R16") (pin "2") (pinfunction "2_2") (pintype "passive"))
      (node (ref "S16") (pin "3") (pinfunction "Vout_3") (pintype "passive"))
    )
  )
)
